# oven_thermocouples.net
KiCad netlist of a schematic drawn in EAGLE
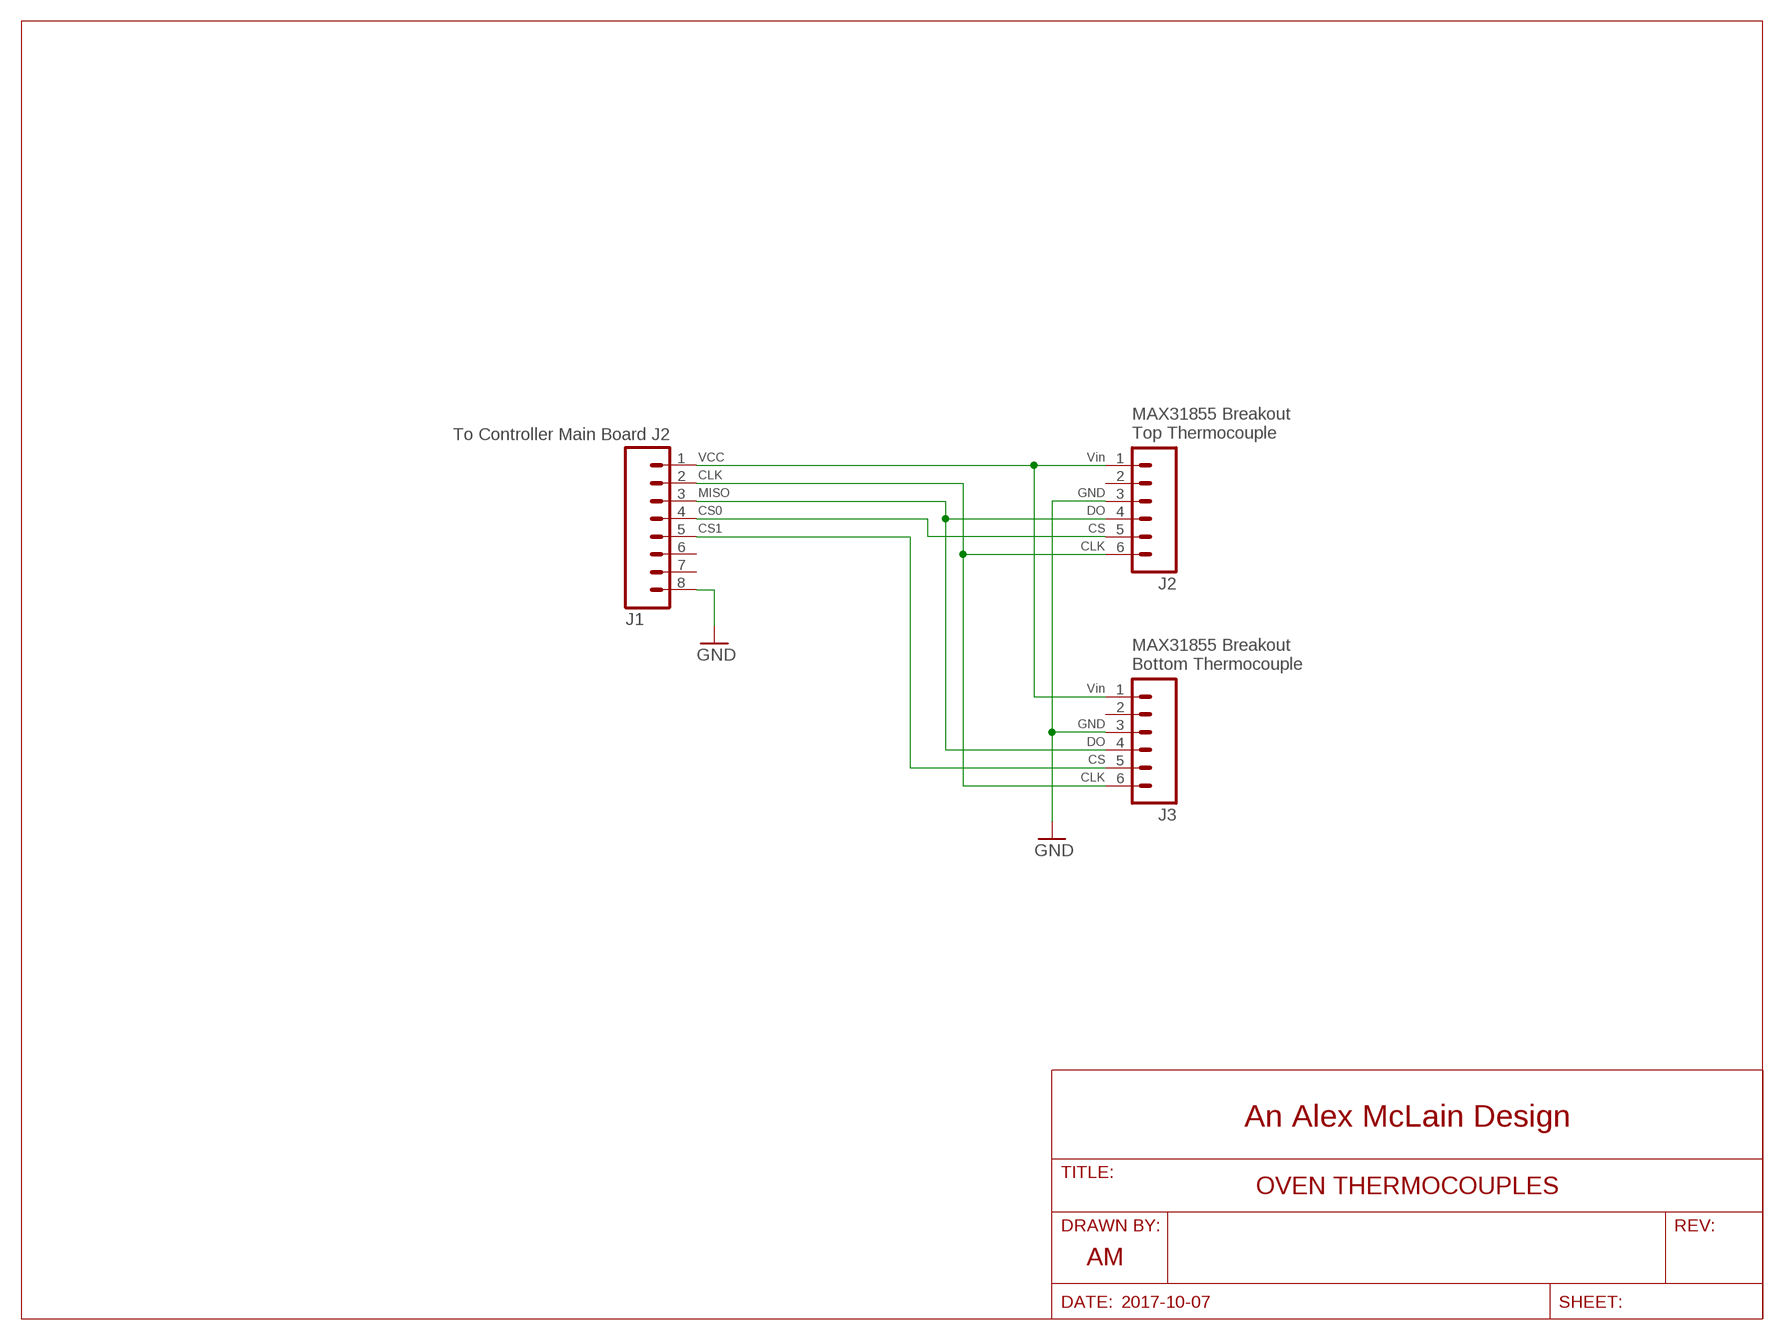
[diagram p0: schematic, sheet 1]

(export (version "E")
  (design (tool "Eeschema 10.0.6"))
  (components
    (comp (ref "J1")
      (value "MA08")
      (footprint "eagle-import:08PA")
      (libsource (lib "eagle-import") (part "MA08"))
    )
    (comp (ref "J2")
      (value "MA06")
      (footprint "eagle-import:06PA")
      (libsource (lib "eagle-import") (part "MA06"))
    )
    (comp (ref "J3")
      (value "MA06")
      (footprint "eagle-import:06PA")
      (libsource (lib "eagle-import") (part "MA06"))
    )
  )
  (nets
    (net (code "1") (name "GND") (class "Default")
      (node (ref "J1") (pin "8") (pinfunction "8_8") (pintype "passive"))
      (node (ref "J2") (pin "3") (pinfunction "3_3") (pintype "passive"))
      (node (ref "J3") (pin "3") (pinfunction "3_3") (pintype "passive"))
    )
    (net (code "2") (name "Net-(J1-Pad1)") (class "Default")
      (node (ref "J1") (pin "1") (pinfunction "1_1") (pintype "passive"))
      (node (ref "J2") (pin "1") (pinfunction "1_1") (pintype "passive"))
      (node (ref "J3") (pin "1") (pinfunction "1_1") (pintype "passive"))
    )
    (net (code "3") (name "Net-(J1-Pad2)") (class "Default")
      (node (ref "J1") (pin "2") (pinfunction "2_2") (pintype "passive"))
      (node (ref "J2") (pin "6") (pinfunction "6_6") (pintype "passive"))
      (node (ref "J3") (pin "6") (pinfunction "6_6") (pintype "passive"))
    )
    (net (code "4") (name "Net-(J1-Pad3)") (class "Default")
      (node (ref "J1") (pin "3") (pinfunction "3_3") (pintype "passive"))
      (node (ref "J2") (pin "4") (pinfunction "4_4") (pintype "passive"))
      (node (ref "J3") (pin "4") (pinfunction "4_4") (pintype "passive"))
    )
    (net (code "5") (name "Net-(J1-Pad4)") (class "Default")
      (node (ref "J1") (pin "4") (pinfunction "4_4") (pintype "passive"))
      (node (ref "J2") (pin "5") (pinfunction "5_5") (pintype "passive"))
    )
    (net (code "6") (name "Net-(J1-Pad5)") (class "Default")
      (node (ref "J1") (pin "5") (pinfunction "5_5") (pintype "passive"))
      (node (ref "J3") (pin "5") (pinfunction "5_5") (pintype "passive"))
    )
    (net (code "7") (name "unconnected-(J1-Pad6)") (class "Default")
      (node (ref "J1") (pin "6") (pinfunction "6_6") (pintype "passive"))
    )
    (net (code "8") (name "unconnected-(J1-Pad7)") (class "Default")
      (node (ref "J1") (pin "7") (pinfunction "7_7") (pintype "passive"))
    )
    (net (code "9") (name "unconnected-(J2-Pad2)") (class "Default")
      (node (ref "J2") (pin "2") (pinfunction "2_2") (pintype "passive"))
    )
    (net (code "10") (name "unconnected-(J3-Pad2)") (class "Default")
      (node (ref "J3") (pin "2") (pinfunction "2_2") (pintype "passive"))
    )
  )
)
